# BMCOP_V1_2.net
KiCad netlist of a schematic drawn in EAGLE
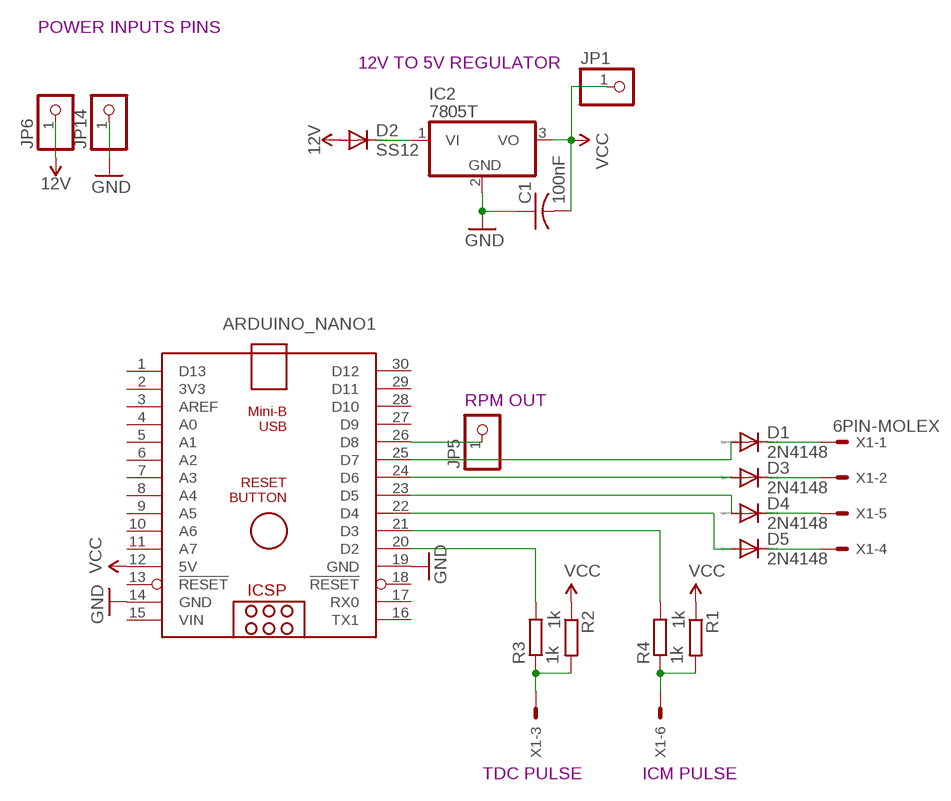
[diagram p0: schematic, sheet 1]

(export (version "E")
  (design (tool "Eeschema 10.0.6"))
  (components
    (comp (ref "ARDUINO_NANO1")
      (value "ARDUINO_NANO")
      (footprint "eagle-import:ARDUINO_NANO")
      (libsource (lib "eagle-import") (part "ARDUINO_NANO"))
    )
    (comp (ref "C1")
      (value "100nF")
      (footprint "eagle-import:C025-024X044")
      (libsource (lib "eagle-import") (part "C-US025-024X044"))
    )
    (comp (ref "D1")
      (value "2N4148")
      (footprint "eagle-import:D-7.5")
      (libsource (lib "eagle-import") (part "DIODE-D-7.5"))
    )
    (comp (ref "D2")
      (value "SS12")
      (footprint "eagle-import:D-7.5")
      (libsource (lib "eagle-import") (part "DIODE-D-7.5"))
    )
    (comp (ref "D3")
      (value "2N4148")
      (footprint "eagle-import:D-7.5")
      (libsource (lib "eagle-import") (part "DIODE-D-7.5"))
    )
    (comp (ref "D4")
      (value "2N4148")
      (footprint "eagle-import:D-7.5")
      (libsource (lib "eagle-import") (part "DIODE-D-7.5"))
    )
    (comp (ref "D5")
      (value "2N4148")
      (footprint "eagle-import:D-7.5")
      (libsource (lib "eagle-import") (part "DIODE-D-7.5"))
    )
    (comp (ref "IC2")
      (value "7805T")
      (footprint "eagle-import:TO220H")
      (libsource (lib "eagle-import") (part "78T05"))
    )
    (comp (ref "JP1")
      (value "PINHD-1X1")
      (footprint "eagle-import:1X01")
      (libsource (lib "eagle-import") (part "PINHD-1X1"))
    )
    (comp (ref "JP5")
      (value "PINHD-1X1")
      (footprint "eagle-import:1X01")
      (libsource (lib "eagle-import") (part "PINHD-1X1"))
    )
    (comp (ref "JP6")
      (value "PINHD-1X1")
      (footprint "eagle-import:1X01")
      (libsource (lib "eagle-import") (part "PINHD-1X1"))
    )
    (comp (ref "JP14")
      (value "PINHD-1X1")
      (footprint "eagle-import:1X01")
      (libsource (lib "eagle-import") (part "PINHD-1X1"))
    )
    (comp (ref "R1")
      (value "1k")
      (footprint "eagle-import:0204_7")
      (libsource (lib "eagle-import") (part "R-EU_0204/7"))
    )
    (comp (ref "R2")
      (value "1k")
      (footprint "eagle-import:0204_7")
      (libsource (lib "eagle-import") (part "R-EU_0204/7"))
    )
    (comp (ref "R3")
      (value "1k")
      (footprint "eagle-import:0204_7")
      (libsource (lib "eagle-import") (part "R-EU_0204/7"))
    )
    (comp (ref "R4")
      (value "1k")
      (footprint "eagle-import:0204_7")
      (libsource (lib "eagle-import") (part "R-EU_0204/7"))
    )
    (comp (ref "X1")
      (value "6PIN-MOLEX")
      (footprint "eagle-import:6PIN-MOLEX")
      (libsource (lib "eagle-import") (part "6PIN-MOLEX"))
    )
  )
  (nets
    (net (code "1") (name "/VIN") (class "Default")
      (node (ref "ARDUINO_NANO1") (pin "15") (pinfunction "VIN_15") (pintype "power_in"))
    )
    (net (code "2") (name "12V") (class "Default")
      (node (ref "D2") (pin "A") (pinfunction "A_A") (pintype "passive"))
      (node (ref "JP6") (pin "1") (pinfunction "1_1") (pintype "passive"))
    )
    (net (code "3") (name "GND") (class "Default")
      (node (ref "ARDUINO_NANO1") (pin "14") (pinfunction "GND_14") (pintype "power_in"))
      (node (ref "ARDUINO_NANO1") (pin "19") (pinfunction "GND_19") (pintype "power_in"))
      (node (ref "C1") (pin "1") (pinfunction "1_1") (pintype "passive"))
      (node (ref "IC2") (pin "2") (pinfunction "GND_2") (pintype "passive"))
      (node (ref "JP14") (pin "1") (pinfunction "1_1") (pintype "passive"))
    )
    (net (code "4") (name "Net-(ARDUINO_NANO1-D2)") (class "Default")
      (node (ref "ARDUINO_NANO1") (pin "20") (pinfunction "D2_20") (pintype "bidirectional"))
      (node (ref "R3") (pin "2") (pinfunction "2_2") (pintype "passive"))
    )
    (net (code "5") (name "Net-(ARDUINO_NANO1-D3)") (class "Default")
      (node (ref "ARDUINO_NANO1") (pin "21") (pinfunction "D3_21") (pintype "bidirectional"))
      (node (ref "R4") (pin "2") (pinfunction "2_2") (pintype "passive"))
    )
    (net (code "6") (name "Net-(ARDUINO_NANO1-D4)") (class "Default")
      (node (ref "ARDUINO_NANO1") (pin "22") (pinfunction "D4_22") (pintype "bidirectional"))
      (node (ref "D5") (pin "A") (pinfunction "A_A") (pintype "passive"))
    )
    (net (code "7") (name "Net-(ARDUINO_NANO1-D5)") (class "Default")
      (node (ref "ARDUINO_NANO1") (pin "23") (pinfunction "D5_23") (pintype "bidirectional"))
      (node (ref "D4") (pin "A") (pinfunction "A_A") (pintype "passive"))
    )
    (net (code "8") (name "Net-(ARDUINO_NANO1-D6)") (class "Default")
      (node (ref "ARDUINO_NANO1") (pin "24") (pinfunction "D6_24") (pintype "bidirectional"))
      (node (ref "D3") (pin "A") (pinfunction "A_A") (pintype "passive"))
    )
    (net (code "9") (name "Net-(ARDUINO_NANO1-D7)") (class "Default")
      (node (ref "ARDUINO_NANO1") (pin "25") (pinfunction "D7_25") (pintype "bidirectional"))
      (node (ref "D1") (pin "A") (pinfunction "A_A") (pintype "passive"))
    )
    (net (code "10") (name "Net-(ARDUINO_NANO1-D8)") (class "Default")
      (node (ref "ARDUINO_NANO1") (pin "26") (pinfunction "D8_26") (pintype "bidirectional"))
      (node (ref "JP5") (pin "1") (pinfunction "1_1") (pintype "passive"))
    )
    (net (code "11") (name "Net-(IC2-VI)") (class "Default")
      (node (ref "D2") (pin "C") (pinfunction "C_C") (pintype "passive"))
      (node (ref "IC2") (pin "1") (pinfunction "VI_1") (pintype "input"))
    )
    (net (code "12") (name "Net-(X1A-S)") (class "Default")
      (node (ref "D1") (pin "C") (pinfunction "C_C") (pintype "passive"))
      (node (ref "X1") (pin "1") (pinfunction "S_1") (pintype "passive"))
    )
    (net (code "13") (name "Net-(X1B-S)") (class "Default")
      (node (ref "D3") (pin "C") (pinfunction "C_C") (pintype "passive"))
      (node (ref "X1") (pin "2") (pinfunction "S_2") (pintype "passive"))
    )
    (net (code "14") (name "Net-(X1C-S)") (class "Default")
      (node (ref "R2") (pin "2") (pinfunction "2_2") (pintype "passive"))
      (node (ref "R3") (pin "1") (pinfunction "1_1") (pintype "passive"))
      (node (ref "X1") (pin "3") (pinfunction "S_3") (pintype "passive"))
    )
    (net (code "15") (name "Net-(X1D-S)") (class "Default")
      (node (ref "D5") (pin "C") (pinfunction "C_C") (pintype "passive"))
      (node (ref "X1") (pin "4") (pinfunction "S_4") (pintype "passive"))
    )
    (net (code "16") (name "Net-(X1E-S)") (class "Default")
      (node (ref "D4") (pin "C") (pinfunction "C_C") (pintype "passive"))
      (node (ref "X1") (pin "5") (pinfunction "S_5") (pintype "passive"))
    )
    (net (code "17") (name "Net-(X1F-S)") (class "Default")
      (node (ref "R1") (pin "2") (pinfunction "2_2") (pintype "passive"))
      (node (ref "R4") (pin "1") (pinfunction "1_1") (pintype "passive"))
      (node (ref "X1") (pin "6") (pinfunction "S_6") (pintype "passive"))
    )
    (net (code "18") (name "VCC") (class "Default")
      (node (ref "ARDUINO_NANO1") (pin "12") (pinfunction "5V_12") (pintype "power_in"))
      (node (ref "C1") (pin "2") (pinfunction "2_2") (pintype "passive"))
      (node (ref "IC2") (pin "3") (pinfunction "VO_3") (pintype "passive"))
      (node (ref "JP1") (pin "1") (pinfunction "1_1") (pintype "passive"))
      (node (ref "R1") (pin "1") (pinfunction "1_1") (pintype "passive"))
      (node (ref "R2") (pin "1") (pinfunction "1_1") (pintype "passive"))
    )
    (net (code "19") (name "unconnected-(ARDUINO_NANO1-3V3-Pad2)") (class "Default")
      (node (ref "ARDUINO_NANO1") (pin "2") (pinfunction "3V3_2") (pintype "output"))
    )
    (net (code "20") (name "unconnected-(ARDUINO_NANO1-A0-Pad4)") (class "Default")
      (node (ref "ARDUINO_NANO1") (pin "4") (pinfunction "A0_4") (pintype "bidirectional"))
    )
    (net (code "21") (name "unconnected-(ARDUINO_NANO1-A1-Pad5)") (class "Default")
      (node (ref "ARDUINO_NANO1") (pin "5") (pinfunction "A1_5") (pintype "bidirectional"))
    )
    (net (code "22") (name "unconnected-(ARDUINO_NANO1-A2-Pad6)") (class "Default")
      (node (ref "ARDUINO_NANO1") (pin "6") (pinfunction "A2_6") (pintype "bidirectional"))
    )
    (net (code "23") (name "unconnected-(ARDUINO_NANO1-A3-Pad7)") (class "Default")
      (node (ref "ARDUINO_NANO1") (pin "7") (pinfunction "A3_7") (pintype "bidirectional"))
    )
    (net (code "24") (name "unconnected-(ARDUINO_NANO1-A4-Pad8)") (class "Default")
      (node (ref "ARDUINO_NANO1") (pin "8") (pinfunction "A4_8") (pintype "bidirectional"))
    )
    (net (code "25") (name "unconnected-(ARDUINO_NANO1-A5-Pad9)") (class "Default")
      (node (ref "ARDUINO_NANO1") (pin "9") (pinfunction "A5_9") (pintype "bidirectional"))
    )
    (net (code "26") (name "unconnected-(ARDUINO_NANO1-A6-Pad10)") (class "Default")
      (node (ref "ARDUINO_NANO1") (pin "10") (pinfunction "A6_10") (pintype "bidirectional"))
    )
    (net (code "27") (name "unconnected-(ARDUINO_NANO1-A7-Pad11)") (class "Default")
      (node (ref "ARDUINO_NANO1") (pin "11") (pinfunction "A7_11") (pintype "bidirectional"))
    )
    (net (code "28") (name "unconnected-(ARDUINO_NANO1-AREF-Pad3)") (class "Default")
      (node (ref "ARDUINO_NANO1") (pin "3") (pinfunction "AREF_3") (pintype "input"))
    )
    (net (code "29") (name "unconnected-(ARDUINO_NANO1-D9-Pad27)") (class "Default")
      (node (ref "ARDUINO_NANO1") (pin "27") (pinfunction "D9_27") (pintype "bidirectional"))
    )
    (net (code "30") (name "unconnected-(ARDUINO_NANO1-D10-Pad28)") (class "Default")
      (node (ref "ARDUINO_NANO1") (pin "28") (pinfunction "D10_28") (pintype "bidirectional"))
    )
    (net (code "31") (name "unconnected-(ARDUINO_NANO1-D11-Pad29)") (class "Default")
      (node (ref "ARDUINO_NANO1") (pin "29") (pinfunction "D11_29") (pintype "bidirectional"))
    )
    (net (code "32") (name "unconnected-(ARDUINO_NANO1-D12-Pad30)") (class "Default")
      (node (ref "ARDUINO_NANO1") (pin "30") (pinfunction "D12_30") (pintype "bidirectional"))
    )
    (net (code "33") (name "unconnected-(ARDUINO_NANO1-D13-Pad1)") (class "Default")
      (node (ref "ARDUINO_NANO1") (pin "1") (pinfunction "D13_1") (pintype "bidirectional"))
    )
    (net (code "34") (name "unconnected-(ARDUINO_NANO1-RX0-Pad17)") (class "Default")
      (node (ref "ARDUINO_NANO1") (pin "17") (pinfunction "RX0_17") (pintype "bidirectional"))
    )
    (net (code "35") (name "unconnected-(ARDUINO_NANO1-TX1-Pad16)") (class "Default")
      (node (ref "ARDUINO_NANO1") (pin "16") (pinfunction "TX1_16") (pintype "bidirectional"))
    )
    (net (code "36") (name "unconnected-(ARDUINO_NANO1-~{RESET}-Pad13)") (class "Default")
      (node (ref "ARDUINO_NANO1") (pin "13") (pinfunction "~{RESET}_13") (pintype "input"))
    )
    (net (code "37") (name "unconnected-(ARDUINO_NANO1-~{RESET}-Pad18)") (class "Default")
      (node (ref "ARDUINO_NANO1") (pin "18") (pinfunction "~{RESET}_18") (pintype "input"))
    )
  )
)
